# K40_MiddleMan_002A.net
KiCad netlist of a schematic drawn in EAGLE
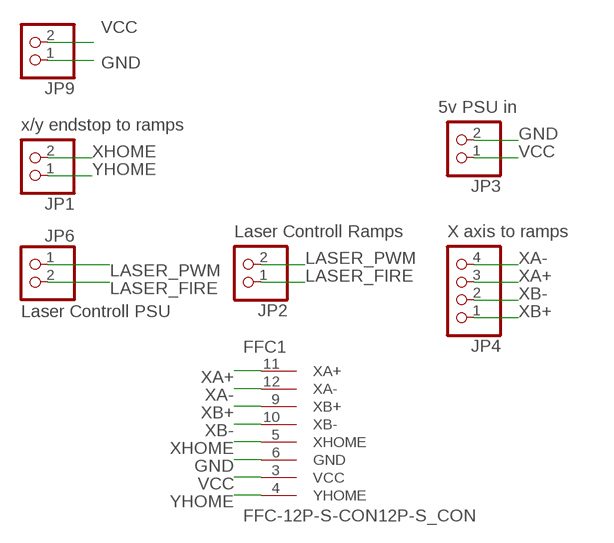
[diagram p0: schematic, sheet 1]

(export (version "E")
  (design (tool "Eeschema 10.0.6"))
  (components
    (comp (ref "FFC1")
      (value "FFC-12P-S-CON12P-S_CON")
      (footprint "eagle-import:FFC")
      (libsource (lib "eagle-import") (part "FFC-12P-S-CON12P-S_CON"))
    )
    (comp (ref "JP1")
      (value "PINHD-1X2")
      (footprint "eagle-import:1X02")
      (libsource (lib "eagle-import") (part "PINHD-1X2"))
    )
    (comp (ref "JP2")
      (value "PINHD-1X2")
      (footprint "eagle-import:1X02")
      (libsource (lib "eagle-import") (part "PINHD-1X2"))
    )
    (comp (ref "JP3")
      (value "PINHD-1X2")
      (footprint "eagle-import:1X02")
      (libsource (lib "eagle-import") (part "PINHD-1X2"))
    )
    (comp (ref "JP4")
      (value "PINHD-1X4")
      (footprint "eagle-import:1X04")
      (libsource (lib "eagle-import") (part "PINHD-1X4"))
    )
    (comp (ref "JP6")
      (value "PINHD-1X2")
      (footprint "eagle-import:1X02")
      (libsource (lib "eagle-import") (part "PINHD-1X2"))
    )
    (comp (ref "JP9")
      (value "PINHD-1X2")
      (footprint "eagle-import:1X02")
      (libsource (lib "eagle-import") (part "PINHD-1X2"))
    )
  )
  (nets
    (net (code "1") (name "/GND") (class "Default")
      (node (ref "FFC1") (pin "6") (pinfunction "GND_6") (pintype "power_in"))
      (node (ref "JP3") (pin "2") (pinfunction "2_2") (pintype "passive"))
      (node (ref "JP9") (pin "1") (pinfunction "1_1") (pintype "passive"))
    )
    (net (code "2") (name "/LASER_FIRE") (class "Default")
      (node (ref "JP2") (pin "1") (pinfunction "1_1") (pintype "passive"))
      (node (ref "JP6") (pin "2") (pinfunction "2_2") (pintype "passive"))
    )
    (net (code "3") (name "/LASER_PWM") (class "Default")
      (node (ref "JP2") (pin "2") (pinfunction "2_2") (pintype "passive"))
      (node (ref "JP6") (pin "1") (pinfunction "1_1") (pintype "passive"))
    )
    (net (code "4") (name "/VCC") (class "Default")
      (node (ref "FFC1") (pin "3") (pinfunction "VCC_3") (pintype "power_in"))
      (node (ref "JP3") (pin "1") (pinfunction "1_1") (pintype "passive"))
      (node (ref "JP9") (pin "2") (pinfunction "2_2") (pintype "passive"))
    )
    (net (code "5") (name "/XA+") (class "Default")
      (node (ref "FFC1") (pin "11") (pinfunction "XA+_11") (pintype "bidirectional"))
      (node (ref "JP4") (pin "3") (pinfunction "3_3") (pintype "passive"))
    )
    (net (code "6") (name "/XA-") (class "Default")
      (node (ref "FFC1") (pin "12") (pinfunction "XA-_12") (pintype "bidirectional"))
      (node (ref "JP4") (pin "4") (pinfunction "4_4") (pintype "passive"))
    )
    (net (code "7") (name "/XB+") (class "Default")
      (node (ref "FFC1") (pin "9") (pinfunction "XB+_9") (pintype "bidirectional"))
      (node (ref "JP4") (pin "1") (pinfunction "1_1") (pintype "passive"))
    )
    (net (code "8") (name "/XB-") (class "Default")
      (node (ref "FFC1") (pin "10") (pinfunction "XB-_10") (pintype "bidirectional"))
      (node (ref "JP4") (pin "2") (pinfunction "2_2") (pintype "passive"))
    )
    (net (code "9") (name "/XHOME") (class "Default")
      (node (ref "FFC1") (pin "5") (pinfunction "XHOME_5") (pintype "bidirectional"))
      (node (ref "JP1") (pin "2") (pinfunction "2_2") (pintype "passive"))
    )
    (net (code "10") (name "/YHOME") (class "Default")
      (node (ref "FFC1") (pin "4") (pinfunction "YHOME_4") (pintype "bidirectional"))
      (node (ref "JP1") (pin "1") (pinfunction "1_1") (pintype "passive"))
    )
  )
)
